# 24x16_RGB_Bottom.net
KiCad netlist of a schematic drawn in EAGLE
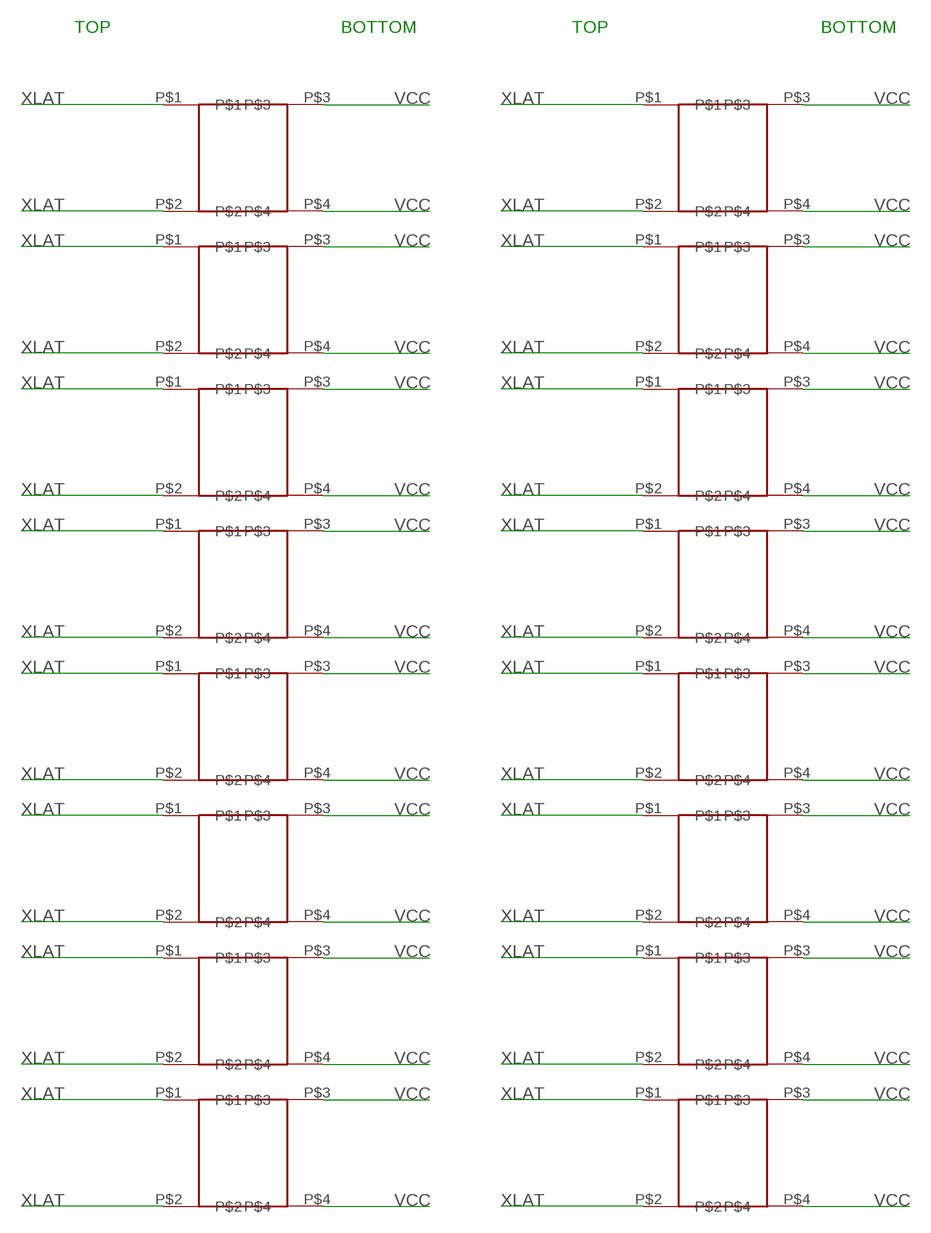
[diagram p0: schematic, sheet 1]
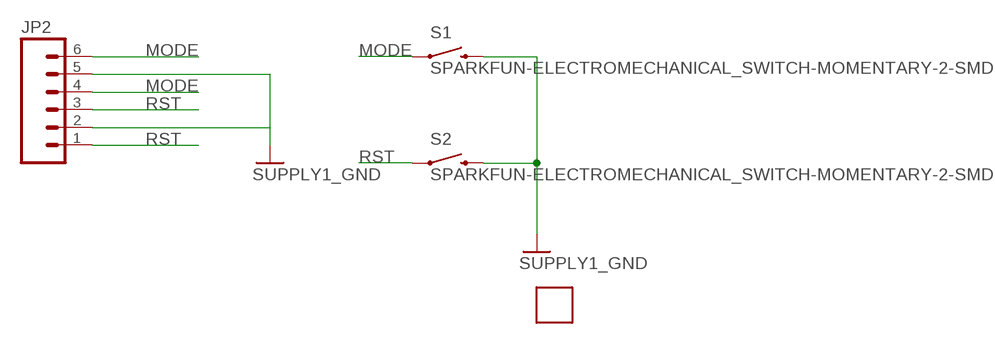
[diagram p1: schematic, sheet 2]

(export (version "E")
  (design (tool "Eeschema 10.0.6"))
  (components
    (comp (ref "JP2")
      (value "M06SIP")
      (footprint "eagle-import:1X06")
      (libsource (lib "eagle-import") (part "M06SIP"))
    )
    (comp (ref "S1")
      (value "SPARKFUN-ELECTROMECHANICAL_SWITCH-MOMENTARY-2-SMD-1101NE")
      (footprint "eagle-import:SPARKFUN-ELECTROMECHANICAL_TACTILE-SWITCH-1101NE")
      (libsource (lib "eagle-import") (part "SPARKFUN-ELECTROMECHANICAL_SWITCH-MOMENTARY-2-SMD-1101NE"))
    )
    (comp (ref "S2")
      (value "SPARKFUN-ELECTROMECHANICAL_SWITCH-MOMENTARY-2-SMD-1101NE")
      (footprint "eagle-import:SPARKFUN-ELECTROMECHANICAL_TACTILE-SWITCH-1101NE")
      (libsource (lib "eagle-import") (part "SPARKFUN-ELECTROMECHANICAL_SWITCH-MOMENTARY-2-SMD-1101NE"))
    )
    (comp (ref "U$1")
      (value "DC_PWR")
      (footprint "eagle-import:DC_2.1")
      (libsource (lib "eagle-import") (part "DC_PWR"))
    )
    (comp (ref "SLOT1")
      (value "SLOT")
      (footprint "eagle-import:SLOT")
      (libsource (lib "eagle-import") (part "SLOT"))
    )
    (comp (ref "SLOT2")
      (value "SLOT")
      (footprint "eagle-import:SLOT")
      (libsource (lib "eagle-import") (part "SLOT"))
    )
    (comp (ref "SLOT3")
      (value "SLOT")
      (footprint "eagle-import:SLOT")
      (libsource (lib "eagle-import") (part "SLOT"))
    )
    (comp (ref "SLOT4")
      (value "SLOT")
      (footprint "eagle-import:SLOT")
      (libsource (lib "eagle-import") (part "SLOT"))
    )
    (comp (ref "SLOT5")
      (value "SLOT")
      (footprint "eagle-import:SLOT")
      (libsource (lib "eagle-import") (part "SLOT"))
    )
    (comp (ref "SLOT6")
      (value "SLOT")
      (footprint "eagle-import:SLOT")
      (libsource (lib "eagle-import") (part "SLOT"))
    )
    (comp (ref "SLOT7")
      (value "SLOT")
      (footprint "eagle-import:SLOT")
      (libsource (lib "eagle-import") (part "SLOT"))
    )
    (comp (ref "SLOT8")
      (value "SLOT")
      (footprint "eagle-import:SLOT")
      (libsource (lib "eagle-import") (part "SLOT"))
    )
    (comp (ref "SLOT9")
      (value "SLOT")
      (footprint "eagle-import:SLOT")
      (libsource (lib "eagle-import") (part "SLOT"))
    )
    (comp (ref "SLOT10")
      (value "SLOT")
      (footprint "eagle-import:SLOT")
      (libsource (lib "eagle-import") (part "SLOT"))
    )
    (comp (ref "SLOT11")
      (value "SLOT")
      (footprint "eagle-import:SLOT")
      (libsource (lib "eagle-import") (part "SLOT"))
    )
    (comp (ref "SLOT12")
      (value "SLOT")
      (footprint "eagle-import:SLOT")
      (libsource (lib "eagle-import") (part "SLOT"))
    )
    (comp (ref "SLOT13")
      (value "SLOT")
      (footprint "eagle-import:SLOT")
      (libsource (lib "eagle-import") (part "SLOT"))
    )
    (comp (ref "SLOT14")
      (value "SLOT")
      (footprint "eagle-import:SLOT")
      (libsource (lib "eagle-import") (part "SLOT"))
    )
    (comp (ref "SLOT15")
      (value "SLOT")
      (footprint "eagle-import:SLOT")
      (libsource (lib "eagle-import") (part "SLOT"))
    )
    (comp (ref "SLOT16")
      (value "SLOT")
      (footprint "eagle-import:SLOT")
      (libsource (lib "eagle-import") (part "SLOT"))
    )
  )
  (nets
    (net (code "1") (name "GND") (class "Default")
      (node (ref "JP2") (pin "2") (pinfunction "2_2") (pintype "passive"))
      (node (ref "JP2") (pin "5") (pinfunction "5_5") (pintype "passive"))
      (node (ref "S1") (pin "P$2") (pinfunction "2_P$2") (pintype "passive"))
      (node (ref "S2") (pin "P$2") (pinfunction "2_P$2") (pintype "passive"))
    )
    (net (code "2") (name "MODE") (class "Default")
      (node (ref "JP2") (pin "4") (pinfunction "4_4") (pintype "passive"))
      (node (ref "JP2") (pin "6") (pinfunction "6_6") (pintype "passive"))
      (node (ref "S1") (pin "P$1") (pinfunction "1_P$1") (pintype "passive"))
    )
    (net (code "3") (name "RST") (class "Default")
      (node (ref "JP2") (pin "1") (pinfunction "1_1") (pintype "passive"))
      (node (ref "JP2") (pin "3") (pinfunction "3_3") (pintype "passive"))
      (node (ref "S2") (pin "P$1") (pinfunction "1_P$1") (pintype "passive"))
    )
    (net (code "4") (name "VCC") (class "Default")
      (node (ref "SLOT1") (pin "P$3") (pinfunction "P$3_P$3") (pintype "bidirectional"))
      (node (ref "SLOT1") (pin "P$4") (pinfunction "P$4_P$4") (pintype "bidirectional"))
      (node (ref "SLOT10") (pin "P$3") (pinfunction "P$3_P$3") (pintype "bidirectional"))
      (node (ref "SLOT10") (pin "P$4") (pinfunction "P$4_P$4") (pintype "bidirectional"))
      (node (ref "SLOT11") (pin "P$3") (pinfunction "P$3_P$3") (pintype "bidirectional"))
      (node (ref "SLOT11") (pin "P$4") (pinfunction "P$4_P$4") (pintype "bidirectional"))
      (node (ref "SLOT12") (pin "P$3") (pinfunction "P$3_P$3") (pintype "bidirectional"))
      (node (ref "SLOT12") (pin "P$4") (pinfunction "P$4_P$4") (pintype "bidirectional"))
      (node (ref "SLOT13") (pin "P$3") (pinfunction "P$3_P$3") (pintype "bidirectional"))
      (node (ref "SLOT13") (pin "P$4") (pinfunction "P$4_P$4") (pintype "bidirectional"))
      (node (ref "SLOT14") (pin "P$3") (pinfunction "P$3_P$3") (pintype "bidirectional"))
      (node (ref "SLOT14") (pin "P$4") (pinfunction "P$4_P$4") (pintype "bidirectional"))
      (node (ref "SLOT15") (pin "P$3") (pinfunction "P$3_P$3") (pintype "bidirectional"))
      (node (ref "SLOT15") (pin "P$4") (pinfunction "P$4_P$4") (pintype "bidirectional"))
      (node (ref "SLOT16") (pin "P$3") (pinfunction "P$3_P$3") (pintype "bidirectional"))
      (node (ref "SLOT16") (pin "P$4") (pinfunction "P$4_P$4") (pintype "bidirectional"))
      (node (ref "SLOT2") (pin "P$3") (pinfunction "P$3_P$3") (pintype "bidirectional"))
      (node (ref "SLOT2") (pin "P$4") (pinfunction "P$4_P$4") (pintype "bidirectional"))
      (node (ref "SLOT3") (pin "P$3") (pinfunction "P$3_P$3") (pintype "bidirectional"))
      (node (ref "SLOT3") (pin "P$4") (pinfunction "P$4_P$4") (pintype "bidirectional"))
      (node (ref "SLOT4") (pin "P$3") (pinfunction "P$3_P$3") (pintype "bidirectional"))
      (node (ref "SLOT4") (pin "P$4") (pinfunction "P$4_P$4") (pintype "bidirectional"))
      (node (ref "SLOT5") (pin "P$3") (pinfunction "P$3_P$3") (pintype "bidirectional"))
      (node (ref "SLOT5") (pin "P$4") (pinfunction "P$4_P$4") (pintype "bidirectional"))
      (node (ref "SLOT6") (pin "P$3") (pinfunction "P$3_P$3") (pintype "bidirectional"))
      (node (ref "SLOT6") (pin "P$4") (pinfunction "P$4_P$4") (pintype "bidirectional"))
      (node (ref "SLOT7") (pin "P$3") (pinfunction "P$3_P$3") (pintype "bidirectional"))
      (node (ref "SLOT7") (pin "P$4") (pinfunction "P$4_P$4") (pintype "bidirectional"))
      (node (ref "SLOT8") (pin "P$3") (pinfunction "P$3_P$3") (pintype "bidirectional"))
      (node (ref "SLOT8") (pin "P$4") (pinfunction "P$4_P$4") (pintype "bidirectional"))
      (node (ref "SLOT9") (pin "P$3") (pinfunction "P$3_P$3") (pintype "bidirectional"))
      (node (ref "SLOT9") (pin "P$4") (pinfunction "P$4_P$4") (pintype "bidirectional"))
    )
    (net (code "5") (name "XLAT") (class "Default")
      (node (ref "SLOT1") (pin "P$1") (pinfunction "P$1_P$1") (pintype "bidirectional"))
      (node (ref "SLOT1") (pin "P$2") (pinfunction "P$2_P$2") (pintype "bidirectional"))
      (node (ref "SLOT10") (pin "P$1") (pinfunction "P$1_P$1") (pintype "bidirectional"))
      (node (ref "SLOT10") (pin "P$2") (pinfunction "P$2_P$2") (pintype "bidirectional"))
      (node (ref "SLOT11") (pin "P$1") (pinfunction "P$1_P$1") (pintype "bidirectional"))
      (node (ref "SLOT11") (pin "P$2") (pinfunction "P$2_P$2") (pintype "bidirectional"))
      (node (ref "SLOT12") (pin "P$1") (pinfunction "P$1_P$1") (pintype "bidirectional"))
      (node (ref "SLOT12") (pin "P$2") (pinfunction "P$2_P$2") (pintype "bidirectional"))
      (node (ref "SLOT13") (pin "P$1") (pinfunction "P$1_P$1") (pintype "bidirectional"))
      (node (ref "SLOT13") (pin "P$2") (pinfunction "P$2_P$2") (pintype "bidirectional"))
      (node (ref "SLOT14") (pin "P$1") (pinfunction "P$1_P$1") (pintype "bidirectional"))
      (node (ref "SLOT14") (pin "P$2") (pinfunction "P$2_P$2") (pintype "bidirectional"))
      (node (ref "SLOT15") (pin "P$1") (pinfunction "P$1_P$1") (pintype "bidirectional"))
      (node (ref "SLOT15") (pin "P$2") (pinfunction "P$2_P$2") (pintype "bidirectional"))
      (node (ref "SLOT16") (pin "P$1") (pinfunction "P$1_P$1") (pintype "bidirectional"))
      (node (ref "SLOT16") (pin "P$2") (pinfunction "P$2_P$2") (pintype "bidirectional"))
      (node (ref "SLOT2") (pin "P$1") (pinfunction "P$1_P$1") (pintype "bidirectional"))
      (node (ref "SLOT2") (pin "P$2") (pinfunction "P$2_P$2") (pintype "bidirectional"))
      (node (ref "SLOT3") (pin "P$1") (pinfunction "P$1_P$1") (pintype "bidirectional"))
      (node (ref "SLOT3") (pin "P$2") (pinfunction "P$2_P$2") (pintype "bidirectional"))
      (node (ref "SLOT4") (pin "P$1") (pinfunction "P$1_P$1") (pintype "bidirectional"))
      (node (ref "SLOT4") (pin "P$2") (pinfunction "P$2_P$2") (pintype "bidirectional"))
      (node (ref "SLOT5") (pin "P$1") (pinfunction "P$1_P$1") (pintype "bidirectional"))
      (node (ref "SLOT5") (pin "P$2") (pinfunction "P$2_P$2") (pintype "bidirectional"))
      (node (ref "SLOT6") (pin "P$1") (pinfunction "P$1_P$1") (pintype "bidirectional"))
      (node (ref "SLOT6") (pin "P$2") (pinfunction "P$2_P$2") (pintype "bidirectional"))
      (node (ref "SLOT7") (pin "P$1") (pinfunction "P$1_P$1") (pintype "bidirectional"))
      (node (ref "SLOT7") (pin "P$2") (pinfunction "P$2_P$2") (pintype "bidirectional"))
      (node (ref "SLOT8") (pin "P$1") (pinfunction "P$1_P$1") (pintype "bidirectional"))
      (node (ref "SLOT8") (pin "P$2") (pinfunction "P$2_P$2") (pintype "bidirectional"))
      (node (ref "SLOT9") (pin "P$1") (pinfunction "P$1_P$1") (pintype "bidirectional"))
      (node (ref "SLOT9") (pin "P$2") (pinfunction "P$2_P$2") (pintype "bidirectional"))
    )
  )
)
